# dimmer.net
KiCad netlist of a schematic drawn in Altium Designer
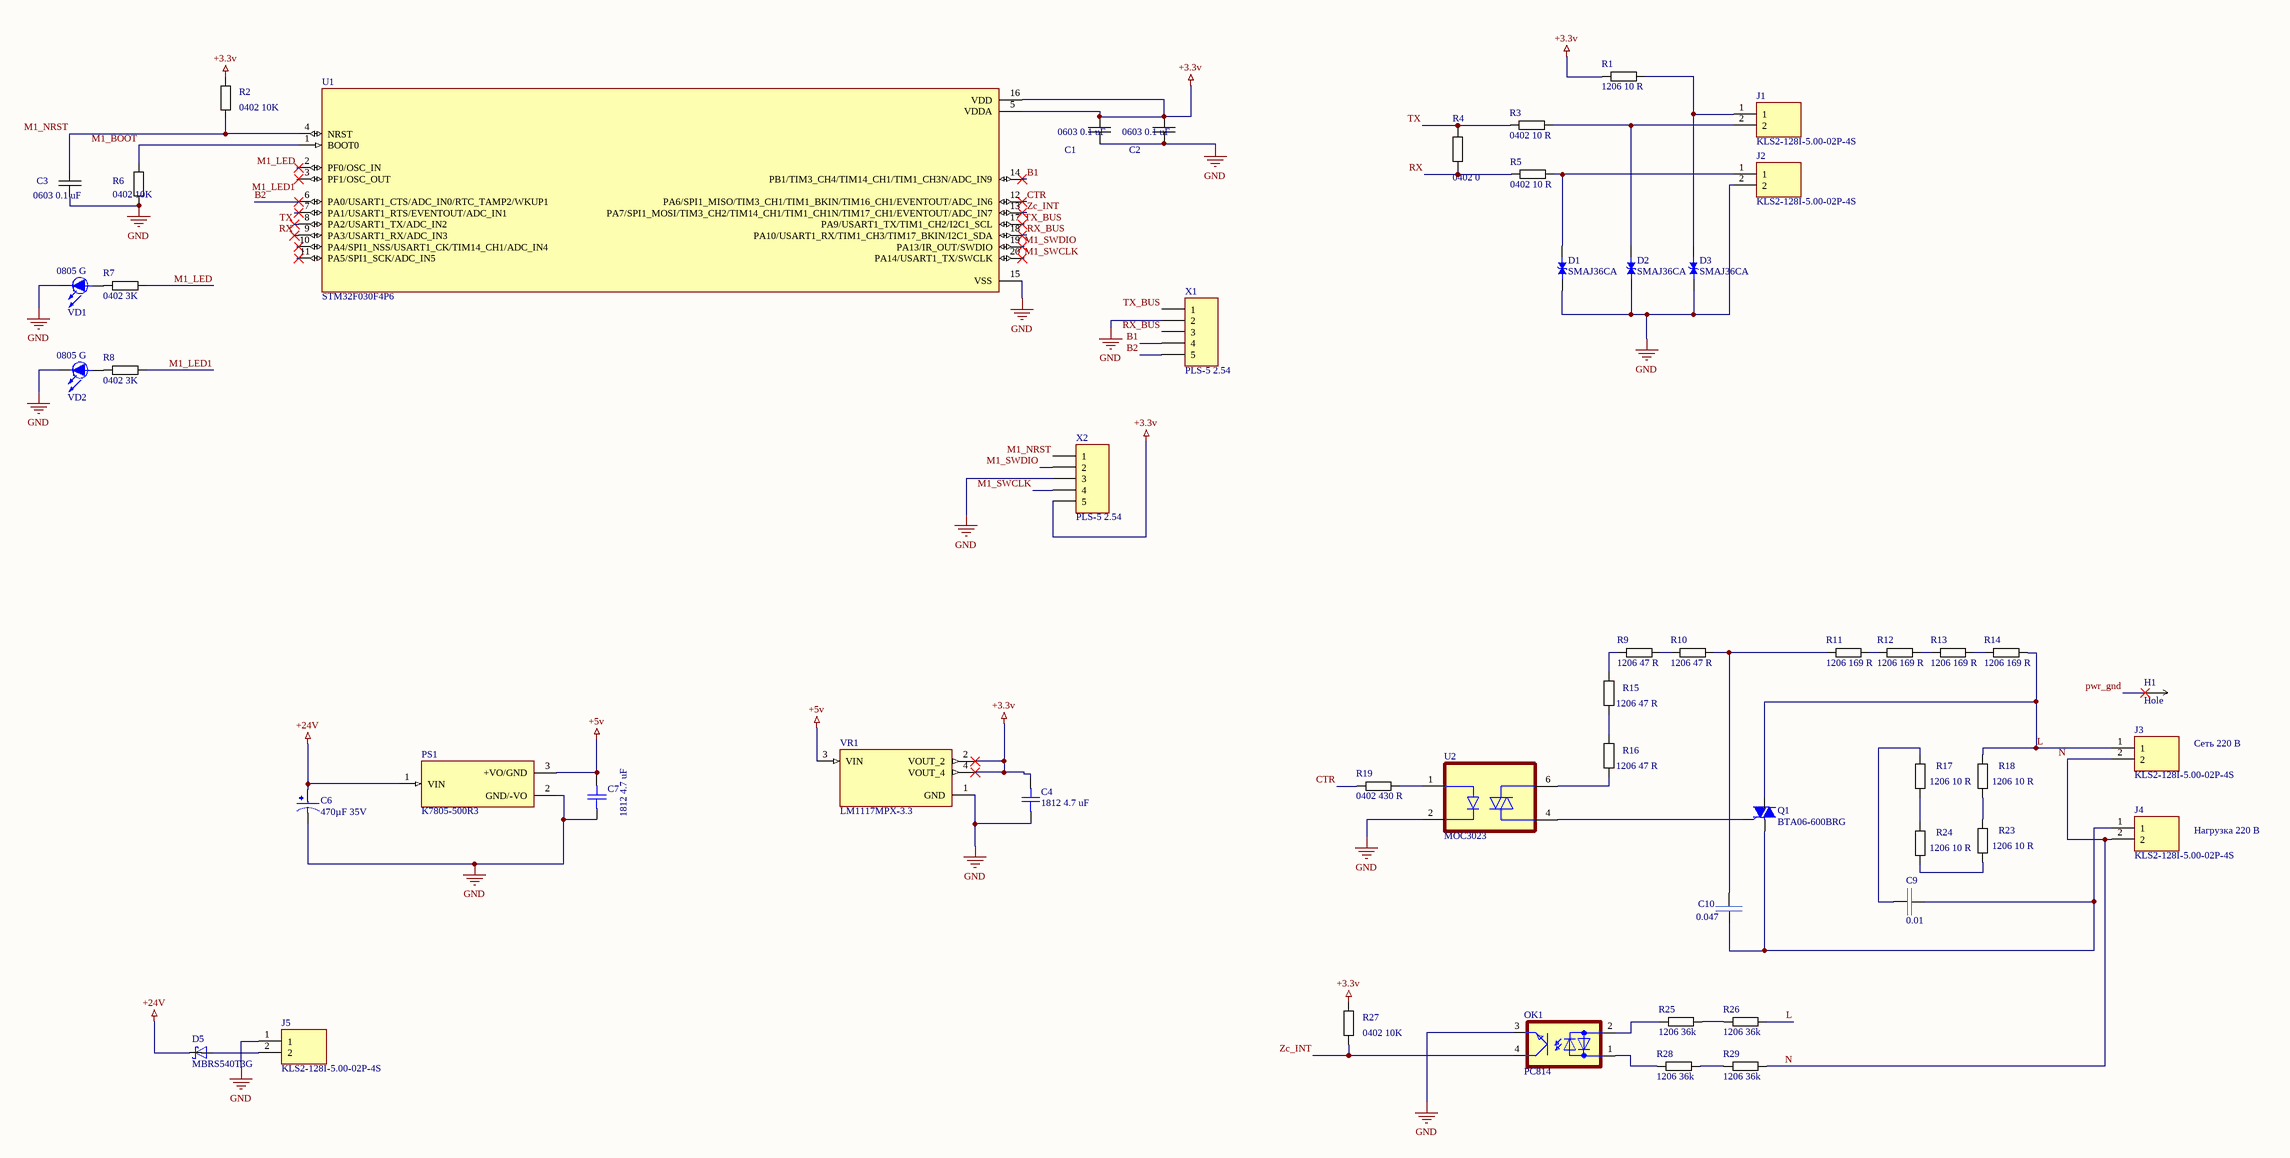
[diagram p0: dimmer.SchDoc]

(export (version "E")
  (design (tool "Eeschema 10.0.6"))
  (components
    (comp (ref "C1")
      (value "0603 0.1 uF")
      (footprint "CAPACITOR 0603")
      (description "Ceramic Capacitor")
      (libsource (lib "Maks_lib") (part "Capasitor"))
    )
    (comp (ref "C2")
      (value "0603 0.1 uF")
      (footprint "CAPACITOR 0603")
      (description "Ceramic Capacitor")
      (libsource (lib "Maks_lib") (part "Capasitor"))
    )
    (comp (ref "C3")
      (value "0603 0.1 uF")
      (footprint "CAPACITOR 0603")
      (description "Ceramic Capacitor")
      (libsource (lib "Maks_lib") (part "Capasitor"))
    )
    (comp (ref "C4")
      (value "1812 4.7 uF")
      (footprint "CAPCHIP1812")
      (description "Ceramic Capacitor")
      (libsource (lib "RCL") (part "Cap C"))
    )
    (comp (ref "C6")
      (value "470µF 35V")
      (footprint "CAP_EEEFK1V471SV")
      (fields (field (name "MP") "EEE-FK1V471SV") (field (name "MF") "Panasonic Electronic Components"))
      (libsource (lib "EEEFK1V471SV") (part "EEEFK1V471SV"))
    )
    (comp (ref "C7")
      (value "1812 4.7 uF")
      (footprint "CAPCHIP1812")
      (description "Ceramic Capacitor")
      (libsource (lib "RCL") (part "Cap C"))
    )
    (comp (ref "C9")
      (value "0.01")
      (footprint "CAPRR1000W60L1300T400H900")
      (libsource (lib "HV_CAP") (part "HV_CAP"))
    )
    (comp (ref "C10")
      (value "0.047")
      (footprint "CAPRR1000W60L1300T400H900")
      (libsource (lib "HV_CAP") (part "HV_CAP"))
    )
    (comp (ref "D1")
      (value "SMAJ36CA")
      (footprint "DIOM4325X250N")
      (libsource (lib "SMAJ36CA") (part "SMAJ36CA"))
    )
    (comp (ref "D2")
      (value "SMAJ36CA")
      (footprint "DIOM4325X250N")
      (libsource (lib "SMAJ36CA") (part "SMAJ36CA"))
    )
    (comp (ref "D3")
      (value "SMAJ36CA")
      (footprint "DIOM4325X250N")
      (libsource (lib "SMAJ36CA") (part "SMAJ36CA"))
    )
    (comp (ref "D5")
      (value "MBRS540T3G")
      (footprint "DIOM7958X213N")
      (description "Diode Schottky 40V 5A Surface Mount SMC")
      (fields (field (name "MF") "ON Semiconductor"))
      (libsource (lib "MBRS540T3G") (part "MBRS540T3G"))
    )
    (comp (ref "H1") (value "Hole") (footprint "Hole 1.5") (libsource (lib "Maks_lib") (part "Hole")))
    (comp (ref "J1")
      (value "KLS2-128I-5.00-02P-4S")
      (footprint "CUI_TB003-500-P02BE")
      (description "2~24 Poles, Screw Type, Horizontal, 5.0 Pitch, 26~14 _AWG_, Terminal Block Connector")
      (fields (field (name "MP") "TB003-500-P02BE") (field (name "MF") "CUI Devices"))
      (libsource (lib "TB003-500-P02BE") (part "TB003-500-P02BE"))
    )
    (comp (ref "J2")
      (value "KLS2-128I-5.00-02P-4S")
      (footprint "CUI_TB003-500-P02BE")
      (description "2~24 Poles, Screw Type, Horizontal, 5.0 Pitch, 26~14 _AWG_, Terminal Block Connector")
      (fields (field (name "MP") "TB003-500-P02BE") (field (name "MF") "CUI Devices"))
      (libsource (lib "TB003-500-P02BE") (part "TB003-500-P02BE"))
    )
    (comp (ref "J3")
      (value "KLS2-128I-5.00-02P-4S")
      (footprint "CUI_TB003-500-P02BE")
      (description "2~24 Poles, Screw Type, Horizontal, 5.0 Pitch, 26~14 _AWG_, Terminal Block Connector")
      (fields (field (name "MP") "TB003-500-P02BE") (field (name "MF") "CUI Devices"))
      (libsource (lib "TB003-500-P02BE") (part "TB003-500-P02BE"))
    )
    (comp (ref "J4")
      (value "KLS2-128I-5.00-02P-4S")
      (footprint "CUI_TB003-500-P02BE")
      (description "2~24 Poles, Screw Type, Horizontal, 5.0 Pitch, 26~14 _AWG_, Terminal Block Connector")
      (fields (field (name "MP") "TB003-500-P02BE") (field (name "MF") "CUI Devices"))
      (libsource (lib "TB003-500-P02BE") (part "TB003-500-P02BE"))
    )
    (comp (ref "J5")
      (value "KLS2-128I-5.00-02P-4S")
      (footprint "CUI_TB003-500-P02BE")
      (description "2~24 Poles, Screw Type, Horizontal, 5.0 Pitch, 26~14 _AWG_, Terminal Block Connector")
      (fields (field (name "MP") "TB003-500-P02BE") (field (name "MF") "CUI Devices"))
      (libsource (lib "TB003-500-P02BE") (part "TB003-500-P02BE"))
    )
    (comp (ref "OK1")
      (value "PC814")
      (footprint "DIL04")
      (description "#10-32 Round Head Machine Screw Slotted Drive Nylon")
      (fields (field (name "MF") "Essentra Components"))
      (libsource (lib "PC814") (part "PC814"))
    )
    (comp (ref "PS1")
      (value "K7805-500R3")
      (footprint "CONV_K7805-500R3")
      (fields (field (name "MF") "MORNSUN"))
      (libsource (lib "K7805-500R3") (part "K7805-500R3"))
    )
    (comp (ref "Q1")
      (value "BTA06-600BRG")
      (footprint "TO254P1040X460X1975-3")
      (description "TRIAC Standard 600V 6A Through Hole TO-220AB")
      (fields (field (name "MF") "STMicroelectronics"))
      (libsource (lib "BTA06-600BRG") (part "BTA06-600BRG"))
    )
    (comp (ref "R1")
      (value "1206 10 R")
      (footprint "Resistor 1206")
      (description "Resistor")
      (libsource (lib "Maks_lib") (part "Resistor"))
    )
    (comp (ref "R2")
      (value "0402 10K")
      (footprint "Resistor 0402")
      (description "Resistor")
      (libsource (lib "Maks_lib") (part "Resistor"))
    )
    (comp (ref "R3")
      (value "0402 10 R")
      (footprint "Resistor 0402")
      (description "Resistor")
      (libsource (lib "Maks_lib") (part "Resistor"))
    )
    (comp (ref "R4")
      (value "0402 0")
      (footprint "Resistor 0402")
      (description "Resistor")
      (libsource (lib "Maks_lib") (part "Resistor"))
    )
    (comp (ref "R5")
      (value "0402 10 R")
      (footprint "Resistor 0402")
      (description "Resistor")
      (libsource (lib "Maks_lib") (part "Resistor"))
    )
    (comp (ref "R6")
      (value "0402 10K")
      (footprint "Resistor 0402")
      (description "Resistor")
      (libsource (lib "Maks_lib") (part "Resistor"))
    )
    (comp (ref "R7")
      (value "0402 3K")
      (footprint "Resistor 0402")
      (description "Resistor")
      (libsource (lib "Maks_lib") (part "Resistor"))
    )
    (comp (ref "R8")
      (value "0402 3K")
      (footprint "Resistor 0402")
      (description "Resistor")
      (libsource (lib "Maks_lib") (part "Resistor"))
    )
    (comp (ref "R9")
      (value "1206 47 R")
      (footprint "Resistor 1206")
      (description "Resistor")
      (libsource (lib "Maks_lib") (part "Resistor"))
    )
    (comp (ref "R10")
      (value "1206 47 R")
      (footprint "Resistor 1206")
      (description "Resistor")
      (libsource (lib "Maks_lib") (part "Resistor"))
    )
    (comp (ref "R11")
      (value "1206 169 R")
      (footprint "Resistor 1206")
      (description "Resistor")
      (libsource (lib "Maks_lib") (part "Resistor"))
    )
    (comp (ref "R12")
      (value "1206 169 R")
      (footprint "Resistor 1206")
      (description "Resistor")
      (libsource (lib "Maks_lib") (part "Resistor"))
    )
    (comp (ref "R13")
      (value "1206 169 R")
      (footprint "Resistor 1206")
      (description "Resistor")
      (libsource (lib "Maks_lib") (part "Resistor"))
    )
    (comp (ref "R14")
      (value "1206 169 R")
      (footprint "Resistor 1206")
      (description "Resistor")
      (libsource (lib "Maks_lib") (part "Resistor"))
    )
    (comp (ref "R15")
      (value "1206 47 R")
      (footprint "Resistor 1206")
      (description "Resistor")
      (libsource (lib "Maks_lib") (part "Resistor"))
    )
    (comp (ref "R16")
      (value "1206 47 R")
      (footprint "Resistor 1206")
      (description "Resistor")
      (libsource (lib "Maks_lib") (part "Resistor"))
    )
    (comp (ref "R17")
      (value "1206 10 R")
      (footprint "Resistor 1206")
      (description "Resistor")
      (libsource (lib "Maks_lib") (part "Resistor"))
    )
    (comp (ref "R18")
      (value "1206 10 R")
      (footprint "Resistor 1206")
      (description "Resistor")
      (libsource (lib "Maks_lib") (part "Resistor"))
    )
    (comp (ref "R19")
      (value "0402 430 R")
      (footprint "Resistor 0402")
      (description "Resistor")
      (libsource (lib "Maks_lib") (part "Resistor"))
    )
    (comp (ref "R23")
      (value "1206 10 R")
      (footprint "Resistor 1206")
      (description "Resistor")
      (libsource (lib "Maks_lib") (part "Resistor"))
    )
    (comp (ref "R24")
      (value "1206 10 R")
      (footprint "Resistor 1206")
      (description "Resistor")
      (libsource (lib "Maks_lib") (part "Resistor"))
    )
    (comp (ref "R25")
      (value "1206 36k")
      (footprint "Resistor 1206")
      (description "Resistor")
      (libsource (lib "Maks_lib") (part "Resistor"))
    )
    (comp (ref "R26")
      (value "1206 36k")
      (footprint "Resistor 1206")
      (description "Resistor")
      (libsource (lib "Maks_lib") (part "Resistor"))
    )
    (comp (ref "R27")
      (value "0402 10K")
      (footprint "Resistor 0402")
      (description "Resistor")
      (libsource (lib "Maks_lib") (part "Resistor"))
    )
    (comp (ref "R28")
      (value "1206 36k")
      (footprint "Resistor 1206")
      (description "Resistor")
      (libsource (lib "Maks_lib") (part "Resistor"))
    )
    (comp (ref "R29")
      (value "1206 36k")
      (footprint "Resistor 1206")
      (description "Resistor")
      (libsource (lib "Maks_lib") (part "Resistor"))
    )
    (comp (ref "U1")
      (value "STM32F030F4P6")
      (footprint "SOP65P640X120-20N")
      (description "MCU 32-bit STM32F ARM Cortex M0 RISC 16KB Flash 2.5V/3.3V 20-Pin TSSOP Tray")
      (libsource (lib "STM32F030F4P6") (part "STM32F030F4P6"))
    )
    (comp (ref "U2")
      (value "MOC3023")
      (footprint "DIP762W48P254L889H508Q6")
      (description "Optoisolator Triac Output 5300Vrms 1 Channel 6-DIP")
      (fields (field (name "MF") "ON Semiconductor"))
      (libsource (lib "MOC3023") (part "MOC3023"))
    )
    (comp (ref "VD1")
      (value "0805 G")
      (footprint "0805-")
      (description "Green")
      (libsource (lib "DT") (part "LED SMD"))
    )
    (comp (ref "VD2")
      (value "0805 G")
      (footprint "0805-")
      (description "Green")
      (libsource (lib "DT") (part "LED SMD"))
    )
    (comp (ref "VR1")
      (value "LM1117MPX-3.3")
      (footprint "VREG_LM1117MPX-3.3")
      (description "800-mA 3.3-V linear voltage regulator")
      (fields (field (name "MF") "Texas Instruments"))
      (libsource (lib "LM1117MPX-3.3") (part "LM1117MPX-3.3"))
    )
    (comp (ref "X1")
      (value "PLS-5 2.54")
      (footprint "PLS-5-3D")
      (description "Header, 5-Pin")
      (fields (field (name "PARTNUMBER") "PLS-5"))
      (libsource (lib "AX_Altium_v2.3") (part "PLS-5"))
    )
    (comp (ref "X2")
      (value "PLS-5 2.54")
      (footprint "PLS-5-3D")
      (description "Header, 5-Pin")
      (fields (field (name "PARTNUMBER") "PLS-5"))
      (libsource (lib "AX_Altium_v2.3") (part "PLS-5"))
    )
  )
  (nets
    (net (code "1") (name "+3.3v") (class "Default")
      (node (ref "C1") (pin "1") (pinfunction "1_1") (pintype "passive"))
      (node (ref "C2") (pin "1") (pinfunction "1_1") (pintype "passive"))
      (node (ref "C4") (pin "1") (pinfunction "1_1") (pintype "passive"))
      (node (ref "R1") (pin "2") (pinfunction "2_2") (pintype "passive"))
      (node (ref "R2") (pin "2") (pinfunction "2_2") (pintype "passive"))
      (node (ref "R27") (pin "2") (pinfunction "2_2") (pintype "passive"))
      (node (ref "U1") (pin "16") (pinfunction "VDD_16") (pintype "power_in"))
      (node (ref "U1") (pin "5") (pinfunction "VDDA_5") (pintype "power_in"))
      (node (ref "VR1") (pin "2") (pinfunction "VOUT_2_2") (pintype "output"))
      (node (ref "VR1") (pin "4") (pinfunction "VOUT_4_4") (pintype "output"))
      (node (ref "X2") (pin "5") (pinfunction "5_5") (pintype "passive"))
    )
    (net (code "2") (name "+5v") (class "Default")
      (node (ref "C7") (pin "2") (pinfunction "2_2") (pintype "passive"))
      (node (ref "PS1") (pin "3") (pinfunction "+VO/GND_3") (pintype "passive"))
      (node (ref "VR1") (pin "3") (pinfunction "VIN_3") (pintype "input"))
    )
    (net (code "3") (name "+24V") (class "Default")
      (node (ref "C6") (pin "1") (pinfunction "1_1") (pintype "passive"))
      (node (ref "D5") (pin "C") (pinfunction "C_C") (pintype "passive"))
      (node (ref "PS1") (pin "1") (pinfunction "VIN_1") (pintype "input"))
    )
    (net (code "4") (name "/B1") (class "Default")
      (node (ref "U1") (pin "14") (pinfunction "PB1/TIM3_CH4/TIM14_CH1/TIM1_CH3N/ADC_IN9_14") (pintype "bidirectional"))
      (node (ref "X1") (pin "4") (pinfunction "4_4") (pintype "passive"))
    )
    (net (code "5") (name "/B2") (class "Default")
      (node (ref "U1") (pin "6") (pinfunction "PA0/USART1_CTS/ADC_IN0/RTC_TAMP2/WKUP1_6") (pintype "bidirectional"))
      (node (ref "X1") (pin "5") (pinfunction "5_5") (pintype "passive"))
    )
    (net (code "6") (name "/CTR") (class "Default")
      (node (ref "R19") (pin "2") (pinfunction "2_2") (pintype "passive"))
      (node (ref "U1") (pin "12") (pinfunction "PA6/SPI1_MISO/TIM3_CH1/TIM1_BKIN/TIM16_CH1/EVENTOUT/ADC_IN6_12") (pintype "bidirectional"))
    )
    (net (code "7") (name "/L") (class "Default")
      (node (ref "J3") (pin "1") (pinfunction "1_1") (pintype "passive"))
      (node (ref "Q1") (pin "2") (pinfunction "A2_2") (pintype "passive"))
      (node (ref "R14") (pin "1") (pinfunction "1_1") (pintype "passive"))
      (node (ref "R18") (pin "2") (pinfunction "2_2") (pintype "passive"))
      (node (ref "R26") (pin "2") (pinfunction "2_2") (pintype "passive"))
    )
    (net (code "8") (name "/M1_BOOT") (class "Default")
      (node (ref "R6") (pin "1") (pinfunction "1_1") (pintype "passive"))
      (node (ref "U1") (pin "1") (pinfunction "BOOT0_1") (pintype "input"))
    )
    (net (code "9") (name "/M1_LED") (class "Default")
      (node (ref "R7") (pin "1") (pinfunction "1_1") (pintype "passive"))
      (node (ref "U1") (pin "2") (pinfunction "PF0/OSC_IN_2") (pintype "bidirectional"))
    )
    (net (code "10") (name "/M1_LED1") (class "Default")
      (node (ref "R8") (pin "1") (pinfunction "1_1") (pintype "passive"))
      (node (ref "U1") (pin "3") (pinfunction "PF1/OSC_OUT_3") (pintype "bidirectional"))
    )
    (net (code "11") (name "/M1_NRST") (class "Default")
      (node (ref "C3") (pin "2") (pinfunction "2_2") (pintype "passive"))
      (node (ref "R2") (pin "1") (pinfunction "1_1") (pintype "passive"))
      (node (ref "U1") (pin "4") (pinfunction "NRST_4") (pintype "bidirectional"))
      (node (ref "X2") (pin "1") (pinfunction "1_1") (pintype "passive"))
    )
    (net (code "12") (name "/M1_SWCLK") (class "Default")
      (node (ref "U1") (pin "20") (pinfunction "PA14/USART1_TX/SWCLK_20") (pintype "bidirectional"))
      (node (ref "X2") (pin "4") (pinfunction "4_4") (pintype "passive"))
    )
    (net (code "13") (name "/M1_SWDIO") (class "Default")
      (node (ref "U1") (pin "19") (pinfunction "PA13/IR_OUT/SWDIO_19") (pintype "bidirectional"))
      (node (ref "X2") (pin "2") (pinfunction "2_2") (pintype "passive"))
    )
    (net (code "14") (name "/N") (class "Default")
      (node (ref "J3") (pin "2") (pinfunction "2_2") (pintype "passive"))
      (node (ref "J4") (pin "2") (pinfunction "2_2") (pintype "passive"))
      (node (ref "R29") (pin "2") (pinfunction "2_2") (pintype "passive"))
    )
    (net (code "15") (name "/RX") (class "Default")
      (node (ref "R4") (pin "2") (pinfunction "2_2") (pintype "passive"))
      (node (ref "R5") (pin "2") (pinfunction "2_2") (pintype "passive"))
      (node (ref "U1") (pin "9") (pinfunction "PA3/USART1_RX/ADC_IN3_9") (pintype "bidirectional"))
    )
    (net (code "16") (name "/RX_BUS") (class "Default")
      (node (ref "U1") (pin "18") (pinfunction "PA10/USART1_RX/TIM1_CH3/TIM17_BKIN/I2C1_SDA_18") (pintype "bidirectional"))
      (node (ref "X1") (pin "3") (pinfunction "3_3") (pintype "passive"))
    )
    (net (code "17") (name "/TX") (class "Default")
      (node (ref "R3") (pin "2") (pinfunction "2_2") (pintype "passive"))
      (node (ref "R4") (pin "1") (pinfunction "1_1") (pintype "passive"))
      (node (ref "U1") (pin "8") (pinfunction "PA2/USART1_TX/ADC_IN2_8") (pintype "bidirectional"))
    )
    (net (code "18") (name "/TX_BUS") (class "Default")
      (node (ref "U1") (pin "17") (pinfunction "PA9/USART1_TX/TIM1_CH2/I2C1_SCL_17") (pintype "bidirectional"))
      (node (ref "X1") (pin "1") (pinfunction "1_1") (pintype "passive"))
    )
    (net (code "19") (name "/Zc_INT") (class "Default")
      (node (ref "OK1") (pin "4") (pinfunction "C_4") (pintype "passive"))
      (node (ref "R27") (pin "1") (pinfunction "1_1") (pintype "passive"))
      (node (ref "U1") (pin "13") (pinfunction "PA7/SPI1_MOSI/TIM3_CH2/TIM14_CH1/TIM1_CH1N/TIM17_CH1/EVENTOUT/ADC_IN7_13") (pintype "bidirectional"))
    )
    (net (code "20") (name "/pwr_gnd") (class "Default")
      (node (ref "H1") (pin "0") (pinfunction "0_0") (pintype "passive+no_connect"))
    )
    (net (code "21") (name "GND") (class "Default")
      (node (ref "C1") (pin "2") (pinfunction "2_2") (pintype "passive"))
      (node (ref "C2") (pin "2") (pinfunction "2_2") (pintype "passive"))
      (node (ref "C3") (pin "1") (pinfunction "1_1") (pintype "passive"))
      (node (ref "C4") (pin "2") (pinfunction "2_2") (pintype "passive"))
      (node (ref "C6") (pin "2") (pinfunction "2_2") (pintype "passive"))
      (node (ref "C7") (pin "1") (pinfunction "1_1") (pintype "passive"))
      (node (ref "D1") (pin "2") (pinfunction "2_2") (pintype "passive"))
      (node (ref "D2") (pin "2") (pinfunction "2_2") (pintype "passive"))
      (node (ref "D3") (pin "2") (pinfunction "2_2") (pintype "passive"))
      (node (ref "J2") (pin "2") (pinfunction "2_2") (pintype "passive"))
      (node (ref "J5") (pin "1") (pinfunction "1_1") (pintype "passive"))
      (node (ref "OK1") (pin "3") (pinfunction "E_3") (pintype "passive"))
      (node (ref "PS1") (pin "2") (pinfunction "GND/-VO_2") (pintype "passive"))
      (node (ref "R6") (pin "2") (pinfunction "2_2") (pintype "passive"))
      (node (ref "U1") (pin "15") (pinfunction "VSS_15") (pintype "power_in"))
      (node (ref "U2") (pin "2") (pinfunction "CATHODE_2") (pintype "passive"))
      (node (ref "VD1") (pin "K") (pinfunction "k_K") (pintype "passive"))
      (node (ref "VD2") (pin "K") (pinfunction "k_K") (pintype "passive"))
      (node (ref "VR1") (pin "1") (pinfunction "GND_1") (pintype "power_in"))
      (node (ref "X1") (pin "2") (pinfunction "2_2") (pintype "passive"))
      (node (ref "X2") (pin "3") (pinfunction "3_3") (pintype "passive"))
    )
    (net (code "22") (name "Net-(C9-Pad2)") (class "Default")
      (node (ref "C9") (pin "2") (pinfunction "2_2") (pintype "passive"))
      (node (ref "R17") (pin "2") (pinfunction "2_2") (pintype "passive"))
    )
    (net (code "23") (name "Net-(C10-Pad1)") (class "Default")
      (node (ref "C10") (pin "1") (pinfunction "1_1") (pintype "passive"))
      (node (ref "R10") (pin "1") (pinfunction "1_1") (pintype "passive"))
      (node (ref "R11") (pin "2") (pinfunction "2_2") (pintype "passive"))
    )
    (net (code "24") (name "Net-(D1-Pad1)") (class "Default")
      (node (ref "D1") (pin "1") (pinfunction "1_1") (pintype "passive"))
      (node (ref "J2") (pin "1") (pinfunction "1_1") (pintype "passive"))
      (node (ref "R5") (pin "1") (pinfunction "1_1") (pintype "passive"))
    )
    (net (code "25") (name "Net-(D2-Pad1)") (class "Default")
      (node (ref "D2") (pin "1") (pinfunction "1_1") (pintype "passive"))
      (node (ref "J1") (pin "2") (pinfunction "2_2") (pintype "passive"))
      (node (ref "R3") (pin "1") (pinfunction "1_1") (pintype "passive"))
    )
    (net (code "26") (name "Net-(D3-Pad1)") (class "Default")
      (node (ref "D3") (pin "1") (pinfunction "1_1") (pintype "passive"))
      (node (ref "J1") (pin "1") (pinfunction "1_1") (pintype "passive"))
      (node (ref "R1") (pin "1") (pinfunction "1_1") (pintype "passive"))
    )
    (net (code "27") (name "Net-(D5-PadA)") (class "Default")
      (node (ref "D5") (pin "A") (pinfunction "A_A") (pintype "passive"))
      (node (ref "J5") (pin "2") (pinfunction "2_2") (pintype "passive"))
    )
    (net (code "28") (name "Net-(OK1-AC1)") (class "Default")
      (node (ref "OK1") (pin "1") (pinfunction "AC1_1") (pintype "passive"))
      (node (ref "R28") (pin "1") (pinfunction "1_1") (pintype "passive"))
    )
    (net (code "29") (name "Net-(OK1-AC2)") (class "Default")
      (node (ref "OK1") (pin "2") (pinfunction "AC2_2") (pintype "passive"))
      (node (ref "R25") (pin "1") (pinfunction "1_1") (pintype "passive"))
    )
    (net (code "30") (name "Net-(Q1-A1)") (class "Default")
      (node (ref "C10") (pin "2") (pinfunction "2_2") (pintype "passive"))
      (node (ref "C9") (pin "1") (pinfunction "1_1") (pintype "passive"))
      (node (ref "J4") (pin "1") (pinfunction "1_1") (pintype "passive"))
      (node (ref "Q1") (pin "1") (pinfunction "A1_1") (pintype "passive"))
    )
    (net (code "31") (name "Net-(Q1-G)") (class "Default")
      (node (ref "Q1") (pin "3") (pinfunction "G_3") (pintype "passive"))
      (node (ref "U2") (pin "4") (pinfunction "MAINTERMINAL_1_4") (pintype "passive"))
    )
    (net (code "32") (name "Net-(R10-Pad2)") (class "Default")
      (node (ref "R10") (pin "2") (pinfunction "2_2") (pintype "passive"))
      (node (ref "R9") (pin "1") (pinfunction "1_1") (pintype "passive"))
    )
    (net (code "33") (name "Net-(R11-Pad1)") (class "Default")
      (node (ref "R11") (pin "1") (pinfunction "1_1") (pintype "passive"))
      (node (ref "R12") (pin "2") (pinfunction "2_2") (pintype "passive"))
    )
    (net (code "34") (name "Net-(R12-Pad1)") (class "Default")
      (node (ref "R12") (pin "1") (pinfunction "1_1") (pintype "passive"))
      (node (ref "R13") (pin "2") (pinfunction "2_2") (pintype "passive"))
    )
    (net (code "35") (name "Net-(R13-Pad1)") (class "Default")
      (node (ref "R13") (pin "1") (pinfunction "1_1") (pintype "passive"))
      (node (ref "R14") (pin "2") (pinfunction "2_2") (pintype "passive"))
    )
    (net (code "36") (name "Net-(R15-Pad1)") (class "Default")
      (node (ref "R15") (pin "1") (pinfunction "1_1") (pintype "passive"))
      (node (ref "R9") (pin "2") (pinfunction "2_2") (pintype "passive"))
    )
    (net (code "37") (name "Net-(R15-Pad2)") (class "Default")
      (node (ref "R15") (pin "2") (pinfunction "2_2") (pintype "passive"))
      (node (ref "R16") (pin "1") (pinfunction "1_1") (pintype "passive"))
    )
    (net (code "38") (name "Net-(R17-Pad1)") (class "Default")
      (node (ref "R17") (pin "1") (pinfunction "1_1") (pintype "passive"))
      (node (ref "R24") (pin "2") (pinfunction "2_2") (pintype "passive"))
    )
    (net (code "39") (name "Net-(R18-Pad1)") (class "Default")
      (node (ref "R18") (pin "1") (pinfunction "1_1") (pintype "passive"))
      (node (ref "R23") (pin "2") (pinfunction "2_2") (pintype "passive"))
    )
    (net (code "40") (name "Net-(R23-Pad1)") (class "Default")
      (node (ref "R23") (pin "1") (pinfunction "1_1") (pintype "passive"))
      (node (ref "R24") (pin "1") (pinfunction "1_1") (pintype "passive"))
    )
    (net (code "41") (name "Net-(R25-Pad2)") (class "Default")
      (node (ref "R25") (pin "2") (pinfunction "2_2") (pintype "passive"))
      (node (ref "R26") (pin "1") (pinfunction "1_1") (pintype "passive"))
    )
    (net (code "42") (name "Net-(R28-Pad2)") (class "Default")
      (node (ref "R28") (pin "2") (pinfunction "2_2") (pintype "passive"))
      (node (ref "R29") (pin "1") (pinfunction "1_1") (pintype "passive"))
    )
    (net (code "43") (name "Net-(U2-ANODE)") (class "Default")
      (node (ref "R19") (pin "1") (pinfunction "1_1") (pintype "passive"))
      (node (ref "U2") (pin "1") (pinfunction "ANODE_1") (pintype "passive"))
    )
    (net (code "44") (name "Net-(U2-MAINTERMINAL_2)") (class "Default")
      (node (ref "R16") (pin "2") (pinfunction "2_2") (pintype "passive"))
      (node (ref "U2") (pin "6") (pinfunction "MAINTERMINAL_2_6") (pintype "passive"))
    )
    (net (code "45") (name "Net-(VD1-a)") (class "Default")
      (node (ref "R7") (pin "2") (pinfunction "2_2") (pintype "passive"))
      (node (ref "VD1") (pin "A") (pinfunction "a_A") (pintype "passive"))
    )
    (net (code "46") (name "Net-(VD2-a)") (class "Default")
      (node (ref "R8") (pin "2") (pinfunction "2_2") (pintype "passive"))
      (node (ref "VD2") (pin "A") (pinfunction "a_A") (pintype "passive"))
    )
    (net (code "47") (name "unconnected-(U1-PA1{slash}USART1_RTS{slash}EVENTOUT{slash}ADC_IN1-Pad7)") (class "Default")
      (node (ref "U1") (pin "7") (pinfunction "PA1/USART1_RTS/EVENTOUT/ADC_IN1_7") (pintype "bidirectional+no_connect"))
    )
    (net (code "48") (name "unconnected-(U1-PA4{slash}SPI1_NSS{slash}USART1_CK{slash}TIM14_CH1{slash}ADC_IN4-Pad10)") (class "Default")
      (node (ref "U1") (pin "10") (pinfunction "PA4/SPI1_NSS/USART1_CK/TIM14_CH1/ADC_IN4_10") (pintype "bidirectional+no_connect"))
    )
    (net (code "49") (name "unconnected-(U1-PA5{slash}SPI1_SCK{slash}ADC_IN5-Pad11)") (class "Default")
      (node (ref "U1") (pin "11") (pinfunction "PA5/SPI1_SCK/ADC_IN5_11") (pintype "bidirectional+no_connect"))
    )
  )
)
